# MCU.net
KiCad netlist of a schematic drawn in Altium Designer
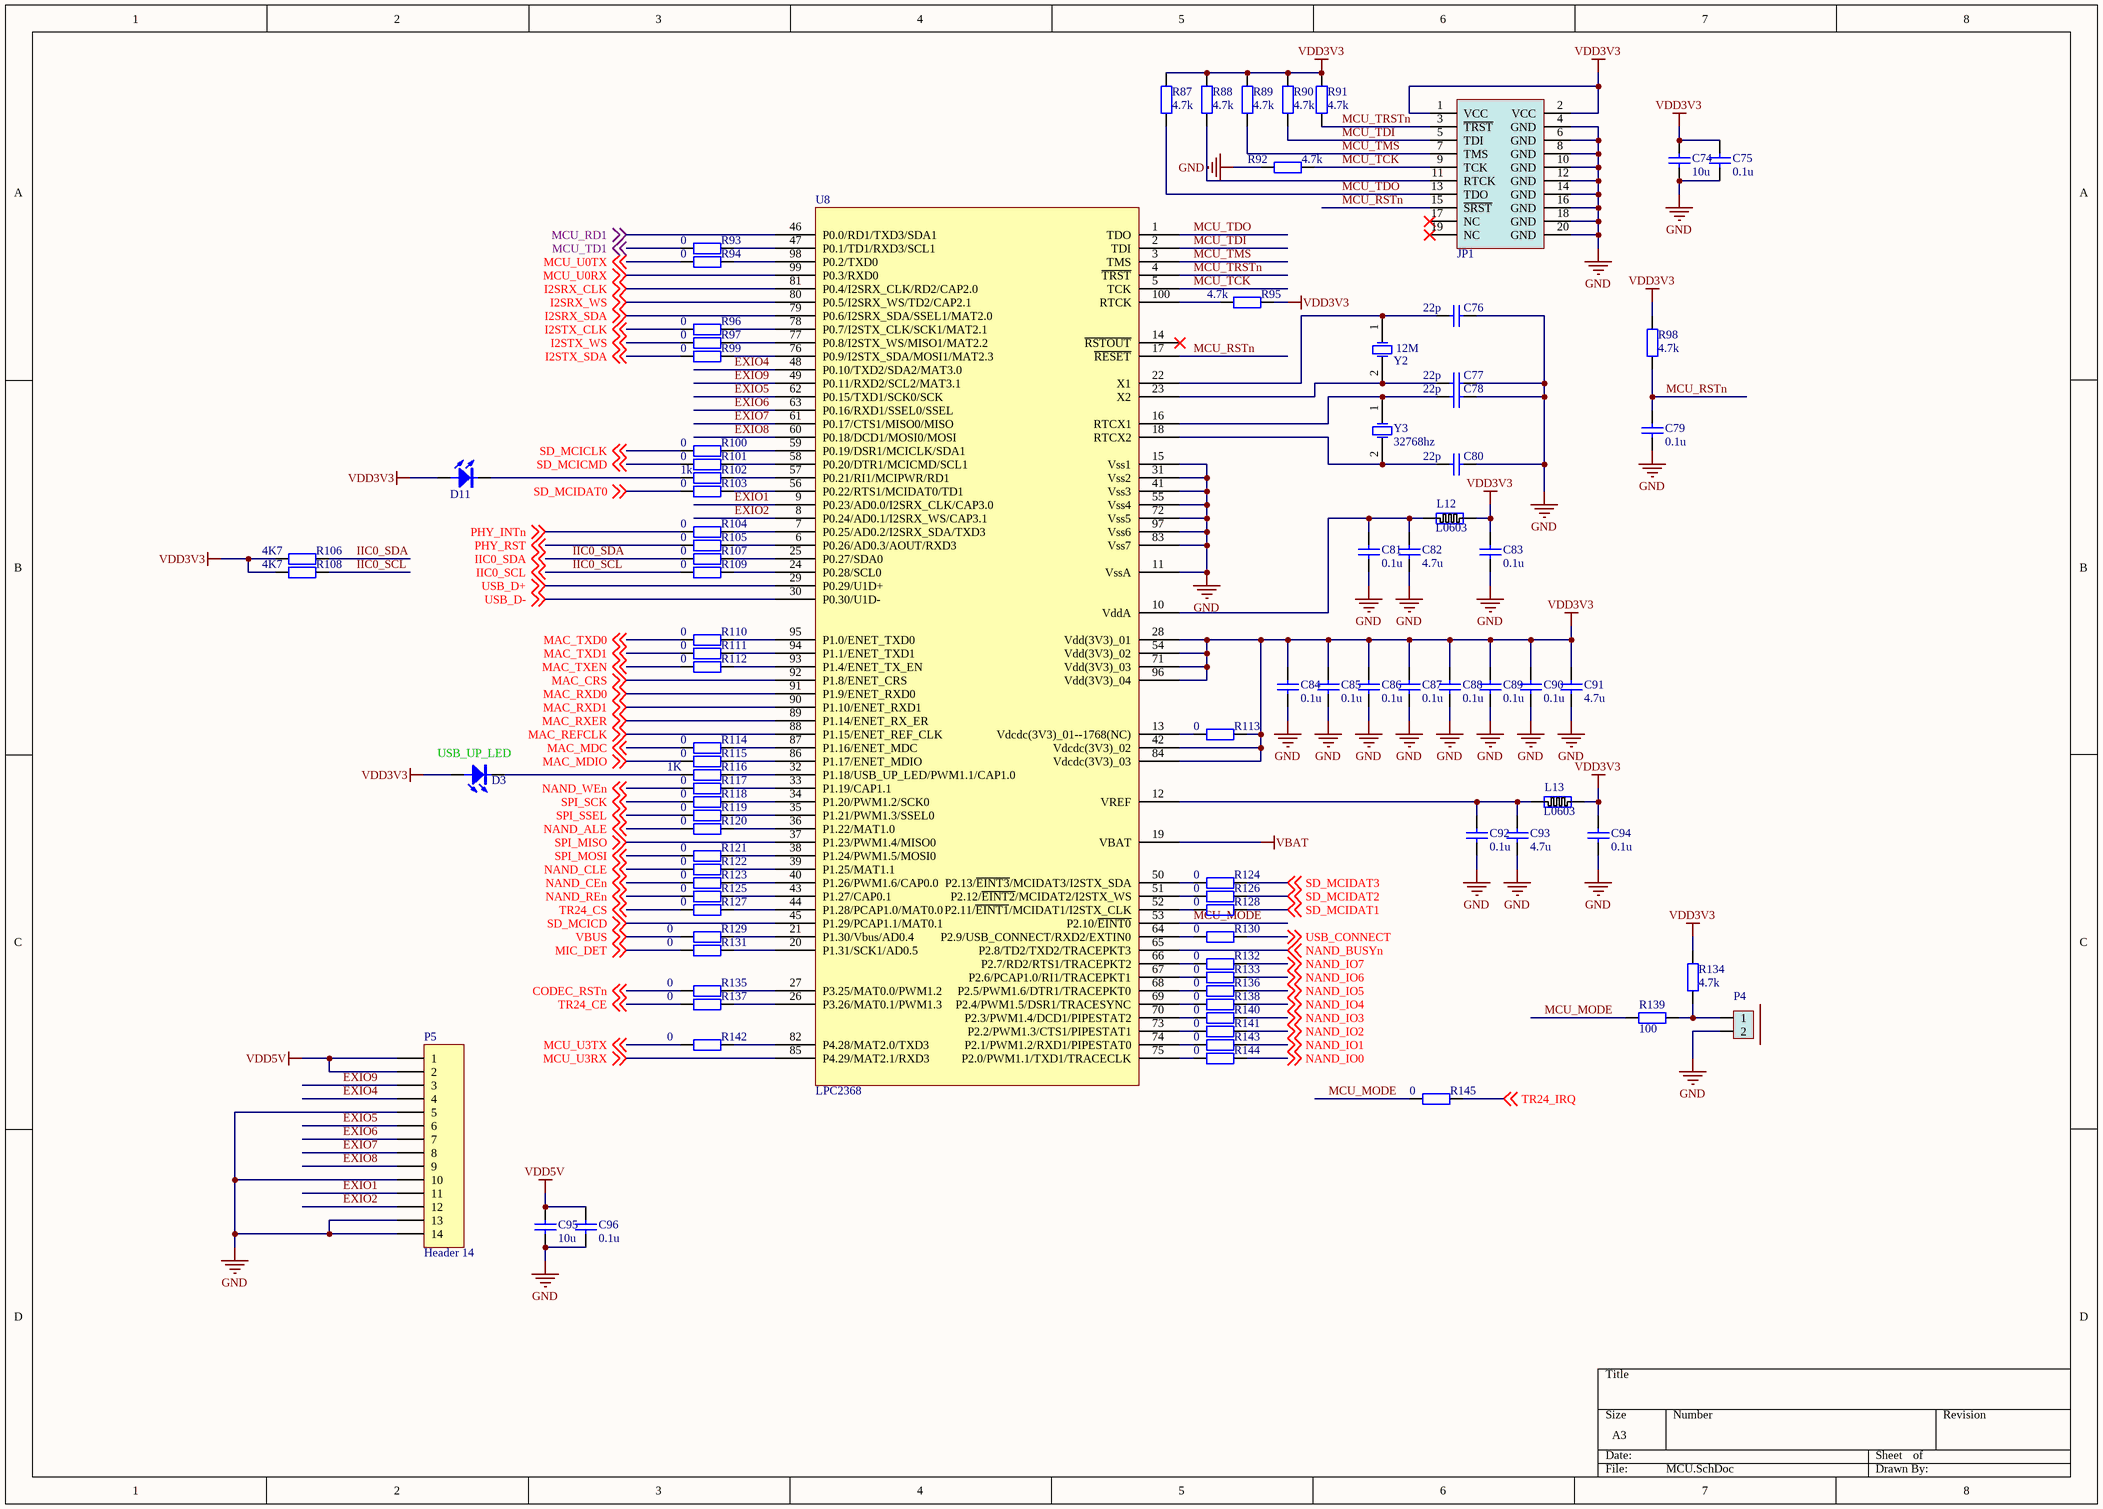
[diagram p0: MCU.SchDoc]

(export (version "E")
  (design (tool "Eeschema 10.0.6"))
  (components
    (comp (ref "C74")
      (value "10u")
      (footprint "C0603")
      (description "0603 Capacitor without Polarity")
      (libsource (lib "lpc2368") (part "CAP0603"))
    )
    (comp (ref "C75")
      (value "0.1u")
      (footprint "C0603")
      (description "0603 Capacitor without Polarity")
      (libsource (lib "lpc2368") (part "CAP0603"))
    )
    (comp (ref "C76")
      (value "22p")
      (footprint "C0603")
      (description "0603 Capacitor without Polarity")
      (libsource (lib "lpc2368") (part "CAP0603"))
    )
    (comp (ref "C77")
      (value "22p")
      (footprint "C0603")
      (description "0603 Capacitor without Polarity")
      (libsource (lib "lpc2368") (part "CAP0603"))
    )
    (comp (ref "C78")
      (value "22p")
      (footprint "C0603")
      (description "0603 Capacitor without Polarity")
      (libsource (lib "lpc2368") (part "CAP0603"))
    )
    (comp (ref "C79")
      (value "0.1u")
      (footprint "C0603")
      (description "0603 Capacitor without Polarity")
      (libsource (lib "lpc2368") (part "CAP0603"))
    )
    (comp (ref "C80")
      (value "22p")
      (footprint "C0603")
      (description "0603 Capacitor without Polarity")
      (libsource (lib "lpc2368") (part "CAP0603"))
    )
    (comp (ref "C81")
      (value "0.1u")
      (footprint "C0603")
      (description "0603 Capacitor without Polarity")
      (libsource (lib "lpc2368") (part "CAP0603"))
    )
    (comp (ref "C82")
      (value "4.7u")
      (footprint "C0603")
      (description "0603 Capacitor without Polarity")
      (libsource (lib "lpc2368") (part "CAP0603"))
    )
    (comp (ref "C83")
      (value "0.1u")
      (footprint "C0603")
      (description "0603 Capacitor without Polarity")
      (libsource (lib "lpc2368") (part "CAP0603"))
    )
    (comp (ref "C84")
      (value "0.1u")
      (footprint "C0603")
      (description "0603 Capacitor without Polarity")
      (libsource (lib "lpc2368") (part "CAP0603"))
    )
    (comp (ref "C85")
      (value "0.1u")
      (footprint "C0603")
      (description "0603 Capacitor without Polarity")
      (libsource (lib "lpc2368") (part "CAP0603"))
    )
    (comp (ref "C86")
      (value "0.1u")
      (footprint "C0603")
      (description "0603 Capacitor without Polarity")
      (libsource (lib "lpc2368") (part "CAP0603"))
    )
    (comp (ref "C87")
      (value "0.1u")
      (footprint "C0603")
      (description "0603 Capacitor without Polarity")
      (libsource (lib "lpc2368") (part "CAP0603"))
    )
    (comp (ref "C88")
      (value "0.1u")
      (footprint "C0603")
      (description "0603 Capacitor without Polarity")
      (libsource (lib "lpc2368") (part "CAP0603"))
    )
    (comp (ref "C89")
      (value "0.1u")
      (footprint "C0603")
      (description "0603 Capacitor without Polarity")
      (libsource (lib "lpc2368") (part "CAP0603"))
    )
    (comp (ref "C90")
      (value "0.1u")
      (footprint "C0603")
      (description "0603 Capacitor without Polarity")
      (libsource (lib "lpc2368") (part "CAP0603"))
    )
    (comp (ref "C91")
      (value "4.7u")
      (footprint "C0603")
      (description "0603 Capacitor without Polarity")
      (libsource (lib "lpc2368") (part "CAP0603"))
    )
    (comp (ref "C92")
      (value "0.1u")
      (footprint "C0603")
      (description "0603 Capacitor without Polarity")
      (libsource (lib "lpc2368") (part "CAP0603"))
    )
    (comp (ref "C93")
      (value "4.7u")
      (footprint "C0603")
      (description "0603 Capacitor without Polarity")
      (libsource (lib "lpc2368") (part "CAP0603"))
    )
    (comp (ref "C94")
      (value "0.1u")
      (footprint "C0603")
      (description "0603 Capacitor without Polarity")
      (libsource (lib "lpc2368") (part "CAP0603"))
    )
    (comp (ref "C95")
      (value "10u")
      (footprint "C0603")
      (description "0603 Capacitor without Polarity")
      (libsource (lib "lpc2368") (part "CAP0603"))
    )
    (comp (ref "C96")
      (value "0.1u")
      (footprint "C0603")
      (description "0603 Capacitor without Polarity")
      (libsource (lib "lpc2368") (part "CAP0603"))
    )
    (comp (ref "D3")
      (value "LED_SMT")
      (footprint "LED0805")
      (description "贴片发光二极管")
      (libsource (lib "lpc2368") (part "LED_SMT"))
    )
    (comp (ref "D11")
      (value "LED_SMT")
      (footprint "LED0805")
      (description "贴片发光二极管")
      (libsource (lib "lpc2368") (part "LED_SMT"))
    )
    (comp (ref "JP1")
      (value "JTAG20")
      (footprint "IDC-20(2.54)IDE")
      (description "JLINK-Interface")
      (libsource (lib "lpc2368") (part "JTAG20"))
    )
    (comp (ref "L12")
      (value "L0603")
      (footprint "L0603")
      (description "0603 Inductor")
      (libsource (lib "lpc2368") (part "L0603"))
    )
    (comp (ref "L13")
      (value "L0603")
      (footprint "L0603")
      (description "0603 Inductor")
      (libsource (lib "lpc2368") (part "L0603"))
    )
    (comp (ref "P4")
      (value "PIN")
      (footprint "SIP2")
      (description "Connectors with two pins")
      (libsource (lib "lpc2368") (part "SIP2"))
    )
    (comp (ref "P5")
      (value "Header 14")
      (footprint "HDR1X14")
      (description "Header, 14-Pin")
      (fields (field (name "PUBLISHER") "Altium Limited"))
      (libsource (lib "Miscellaneous Connectors") (part "Header 14"))
    )
    (comp (ref "R87")
      (value "4.7k")
      (footprint "R0603")
      (description "0603 Resistor")
      (libsource (lib "") (part "RES0603_1"))
    )
    (comp (ref "R88")
      (value "4.7k")
      (footprint "R0603")
      (description "0603 Resistor")
      (libsource (lib "") (part "RES0603_1"))
    )
    (comp (ref "R89")
      (value "4.7k")
      (footprint "R0603")
      (description "0603 Resistor")
      (libsource (lib "") (part "RES0603_1"))
    )
    (comp (ref "R90")
      (value "4.7k")
      (footprint "R0603")
      (description "0603 Resistor")
      (libsource (lib "") (part "RES0603_1"))
    )
    (comp (ref "R91")
      (value "4.7k")
      (footprint "R0603")
      (description "0603 Resistor")
      (libsource (lib "") (part "RES0603_1"))
    )
    (comp (ref "R92")
      (value "4.7k")
      (footprint "R0603")
      (description "0603 Resistor")
      (libsource (lib "") (part "RES0603_2"))
    )
    (comp (ref "R93")
      (value "0")
      (footprint "R0603")
      (description "0603 Resistor")
      (libsource (lib "lpc2368") (part "RES0603"))
    )
    (comp (ref "R94")
      (value "0")
      (footprint "R0603")
      (description "0603 Resistor")
      (libsource (lib "lpc2368") (part "RES0603"))
    )
    (comp (ref "R95")
      (value "4.7k")
      (footprint "R0603")
      (description "0603 Resistor")
      (libsource (lib "lpc2368") (part "RES0603"))
    )
    (comp (ref "R96")
      (value "0")
      (footprint "R0603")
      (description "0603 Resistor")
      (libsource (lib "lpc2368") (part "RES0603"))
    )
    (comp (ref "R97")
      (value "0")
      (footprint "R0603")
      (description "0603 Resistor")
      (libsource (lib "lpc2368") (part "RES0603"))
    )
    (comp (ref "R98")
      (value "4.7k")
      (footprint "R0603")
      (description "0603 Resistor")
      (libsource (lib "") (part "RES0603_1"))
    )
    (comp (ref "R99")
      (value "0")
      (footprint "R0603")
      (description "0603 Resistor")
      (libsource (lib "lpc2368") (part "RES0603"))
    )
    (comp (ref "R100")
      (value "0")
      (footprint "R0603")
      (description "0603 Resistor")
      (libsource (lib "lpc2368") (part "RES0603"))
    )
    (comp (ref "R101")
      (value "0")
      (footprint "R0603")
      (description "0603 Resistor")
      (libsource (lib "lpc2368") (part "RES0603"))
    )
    (comp (ref "R102")
      (value "1k")
      (footprint "R0603")
      (description "0603 Resistor")
      (libsource (lib "lpc2368") (part "RES0603"))
    )
    (comp (ref "R103")
      (value "0")
      (footprint "R0603")
      (description "0603 Resistor")
      (libsource (lib "lpc2368") (part "RES0603"))
    )
    (comp (ref "R104")
      (value "0")
      (footprint "R0603")
      (description "0603 Resistor")
      (libsource (lib "lpc2368") (part "RES0603"))
    )
    (comp (ref "R105")
      (value "0")
      (footprint "R0603")
      (description "0603 Resistor")
      (libsource (lib "lpc2368") (part "RES0603"))
    )
    (comp (ref "R106")
      (value "4K7")
      (footprint "R0603")
      (description "0603 Resistor")
      (libsource (lib "") (part "RES0603_2"))
    )
    (comp (ref "R107")
      (value "0")
      (footprint "R0603")
      (description "0603 Resistor")
      (libsource (lib "lpc2368") (part "RES0603"))
    )
    (comp (ref "R108")
      (value "4K7")
      (footprint "R0603")
      (description "0603 Resistor")
      (libsource (lib "") (part "RES0603_2"))
    )
    (comp (ref "R109")
      (value "0")
      (footprint "R0603")
      (description "0603 Resistor")
      (libsource (lib "lpc2368") (part "RES0603"))
    )
    (comp (ref "R110")
      (value "0")
      (footprint "R0603")
      (description "0603 Resistor")
      (libsource (lib "lpc2368") (part "RES0603"))
    )
    (comp (ref "R111")
      (value "0")
      (footprint "R0603")
      (description "0603 Resistor")
      (libsource (lib "lpc2368") (part "RES0603"))
    )
    (comp (ref "R112")
      (value "0")
      (footprint "R0603")
      (description "0603 Resistor")
      (libsource (lib "lpc2368") (part "RES0603"))
    )
    (comp (ref "R113")
      (value "0")
      (footprint "R0603")
      (description "0603 Resistor")
      (libsource (lib "lpc2368") (part "RES0603"))
    )
    (comp (ref "R114")
      (value "0")
      (footprint "R0603")
      (description "0603 Resistor")
      (libsource (lib "lpc2368") (part "RES0603"))
    )
    (comp (ref "R115")
      (value "0")
      (footprint "R0603")
      (description "0603 Resistor")
      (libsource (lib "lpc2368") (part "RES0603"))
    )
    (comp (ref "R116")
      (value "1K")
      (footprint "R0603")
      (description "0603 Resistor")
      (libsource (lib "lpc2368") (part "RES0603"))
    )
    (comp (ref "R117")
      (value "0")
      (footprint "R0603")
      (description "0603 Resistor")
      (libsource (lib "lpc2368") (part "RES0603"))
    )
    (comp (ref "R118")
      (value "0")
      (footprint "R0603")
      (description "0603 Resistor")
      (libsource (lib "lpc2368") (part "RES0603"))
    )
    (comp (ref "R119")
      (value "0")
      (footprint "R0603")
      (description "0603 Resistor")
      (libsource (lib "lpc2368") (part "RES0603"))
    )
    (comp (ref "R120")
      (value "0")
      (footprint "R0603")
      (description "0603 Resistor")
      (libsource (lib "lpc2368") (part "RES0603"))
    )
    (comp (ref "R121")
      (value "0")
      (footprint "R0603")
      (description "0603 Resistor")
      (libsource (lib "lpc2368") (part "RES0603"))
    )
    (comp (ref "R122")
      (value "0")
      (footprint "R0603")
      (description "0603 Resistor")
      (libsource (lib "lpc2368") (part "RES0603"))
    )
    (comp (ref "R123")
      (value "0")
      (footprint "R0603")
      (description "0603 Resistor")
      (libsource (lib "lpc2368") (part "RES0603"))
    )
    (comp (ref "R124")
      (value "0")
      (footprint "R0603")
      (description "0603 Resistor")
      (libsource (lib "lpc2368") (part "RES0603"))
    )
    (comp (ref "R125")
      (value "0")
      (footprint "R0603")
      (description "0603 Resistor")
      (libsource (lib "lpc2368") (part "RES0603"))
    )
    (comp (ref "R126")
      (value "0")
      (footprint "R0603")
      (description "0603 Resistor")
      (libsource (lib "lpc2368") (part "RES0603"))
    )
    (comp (ref "R127")
      (value "0")
      (footprint "R0603")
      (description "0603 Resistor")
      (libsource (lib "lpc2368") (part "RES0603"))
    )
    (comp (ref "R128")
      (value "0")
      (footprint "R0603")
      (description "0603 Resistor")
      (libsource (lib "lpc2368") (part "RES0603"))
    )
    (comp (ref "R129")
      (value "0")
      (footprint "R0603")
      (description "0603 Resistor")
      (libsource (lib "lpc2368") (part "RES0603"))
    )
    (comp (ref "R130")
      (value "0")
      (footprint "R0603")
      (description "0603 Resistor")
      (libsource (lib "lpc2368") (part "RES0603"))
    )
    (comp (ref "R131")
      (value "0")
      (footprint "R0603")
      (description "0603 Resistor")
      (libsource (lib "lpc2368") (part "RES0603"))
    )
    (comp (ref "R132")
      (value "0")
      (footprint "R0603")
      (description "0603 Resistor")
      (libsource (lib "lpc2368") (part "RES0603"))
    )
    (comp (ref "R133")
      (value "0")
      (footprint "R0603")
      (description "0603 Resistor")
      (libsource (lib "lpc2368") (part "RES0603"))
    )
    (comp (ref "R134")
      (value "4.7k")
      (footprint "R0603")
      (description "0603 Resistor")
      (libsource (lib "") (part "RES0603_1"))
    )
    (comp (ref "R135")
      (value "0")
      (footprint "R0603")
      (description "0603 Resistor")
      (libsource (lib "lpc2368") (part "RES0603"))
    )
    (comp (ref "R136")
      (value "0")
      (footprint "R0603")
      (description "0603 Resistor")
      (libsource (lib "lpc2368") (part "RES0603"))
    )
    (comp (ref "R137")
      (value "0")
      (footprint "R0603")
      (description "0603 Resistor")
      (libsource (lib "lpc2368") (part "RES0603"))
    )
    (comp (ref "R138")
      (value "0")
      (footprint "R0603")
      (description "0603 Resistor")
      (libsource (lib "lpc2368") (part "RES0603"))
    )
    (comp (ref "R139")
      (value "100")
      (footprint "R0603")
      (description "0603 Resistor")
      (libsource (lib "") (part "RES0603_2"))
    )
    (comp (ref "R140")
      (value "0")
      (footprint "R0603")
      (description "0603 Resistor")
      (libsource (lib "lpc2368") (part "RES0603"))
    )
    (comp (ref "R141")
      (value "0")
      (footprint "R0603")
      (description "0603 Resistor")
      (libsource (lib "lpc2368") (part "RES0603"))
    )
    (comp (ref "R142")
      (value "0")
      (footprint "R0603")
      (description "0603 Resistor")
      (libsource (lib "lpc2368") (part "RES0603"))
    )
    (comp (ref "R143")
      (value "0")
      (footprint "R0603")
      (description "0603 Resistor")
      (libsource (lib "lpc2368") (part "RES0603"))
    )
    (comp (ref "R144")
      (value "0")
      (footprint "R0603")
      (description "0603 Resistor")
      (libsource (lib "lpc2368") (part "RES0603"))
    )
    (comp (ref "R145")
      (value "0")
      (footprint "R0603")
      (description "0603 Resistor")
      (libsource (lib "lpc2368") (part "RES0603"))
    )
    (comp (ref "U8")
      (value "LPC2368")
      (footprint "QFP100-I20-605605")
      (libsource (lib "lpc2368") (part "LPC2368"))
    )
    (comp (ref "Y2")
      (value "12M")
      (footprint "XTAL-SMD-LP")
      (description "2Pin晶振")
      (libsource (lib "lpc2368") (part "XTAL"))
    )
    (comp (ref "Y3")
      (value "32768hz")
      (footprint "XTAL32768")
      (description "2Pin晶振")
      (libsource (lib "lpc2368") (part "XTAL32768"))
    )
  )
  (nets
    (net (code "1") (name "/EXIO1") (class "Default")
      (node (ref "P5") (pin "11") (pinfunction "11_11") (pintype "passive"))
      (node (ref "U8") (pin "9") (pinfunction "P0.23/AD0.0/I2SRX_CLK/CAP3.0_9") (pintype "passive"))
    )
    (net (code "2") (name "/EXIO2") (class "Default")
      (node (ref "P5") (pin "12") (pinfunction "12_12") (pintype "passive"))
      (node (ref "U8") (pin "8") (pinfunction "P0.24/AD0.1/I2SRX_WS/CAP3.1_8") (pintype "passive"))
    )
    (net (code "3") (name "/EXIO4") (class "Default")
      (node (ref "P5") (pin "4") (pinfunction "4_4") (pintype "passive"))
      (node (ref "U8") (pin "48") (pinfunction "P0.10/TXD2/SDA2/MAT3.0_48") (pintype "passive"))
    )
    (net (code "4") (name "/EXIO5") (class "Default")
      (node (ref "P5") (pin "6") (pinfunction "6_6") (pintype "passive"))
      (node (ref "U8") (pin "62") (pinfunction "P0.15/TXD1/SCK0/SCK_62") (pintype "passive"))
    )
    (net (code "5") (name "/EXIO6") (class "Default")
      (node (ref "P5") (pin "7") (pinfunction "7_7") (pintype "passive"))
      (node (ref "U8") (pin "63") (pinfunction "P0.16/RXD1/SSEL0/SSEL_63") (pintype "passive"))
    )
    (net (code "6") (name "/EXIO7") (class "Default")
      (node (ref "P5") (pin "8") (pinfunction "8_8") (pintype "passive"))
      (node (ref "U8") (pin "61") (pinfunction "P0.17/CTS1/MISO0/MISO_61") (pintype "passive"))
    )
    (net (code "7") (name "/EXIO8") (class "Default")
      (node (ref "P5") (pin "9") (pinfunction "9_9") (pintype "passive"))
      (node (ref "U8") (pin "60") (pinfunction "P0.18/DCD1/MOSI0/MOSI_60") (pintype "passive"))
    )
    (net (code "8") (name "/EXIO9") (class "Default")
      (node (ref "P5") (pin "3") (pinfunction "3_3") (pintype "passive"))
      (node (ref "U8") (pin "49") (pinfunction "P0.11/RXD2/SCL2/MAT3.1_49") (pintype "passive"))
    )
    (net (code "9") (name "/MCU_MODE") (class "Default")
      (node (ref "R139") (pin "2") (pinfunction "2_2") (pintype "passive"))
      (node (ref "R145") (pin "1") (pinfunction "1_1") (pintype "passive"))
      (node (ref "U8") (pin "53") (pinfunction "P2.10/~{EINT0}_53") (pintype "passive"))
    )
    (net (code "10") (name "/MCU_RSTn") (class "Default")
      (node (ref "C79") (pin "2") (pinfunction "2_2") (pintype "passive"))
      (node (ref "JP1") (pin "15") (pinfunction "~{SRST}_15") (pintype "passive"))
      (node (ref "R98") (pin "1") (pinfunction "1_1") (pintype "passive"))
      (node (ref "U8") (pin "17") (pinfunction "~{RESET}_17") (pintype "passive"))
    )
    (net (code "11") (name "/MCU_TCK") (class "Default")
      (node (ref "JP1") (pin "9") (pinfunction "TCK_9") (pintype "passive"))
      (node (ref "R92") (pin "1") (pinfunction "1_1") (pintype "passive"))
      (node (ref "U8") (pin "5") (pinfunction "TCK_5") (pintype "passive"))
    )
    (net (code "12") (name "/MCU_TDI") (class "Default")
      (node (ref "JP1") (pin "5") (pinfunction "TDI_5") (pintype "passive"))
      (node (ref "R90") (pin "1") (pinfunction "1_1") (pintype "passive"))
      (node (ref "U8") (pin "2") (pinfunction "TDI_2") (pintype "passive"))
    )
    (net (code "13") (name "/MCU_TDO") (class "Default")
      (node (ref "JP1") (pin "13") (pinfunction "TDO_13") (pintype "passive"))
      (node (ref "R87") (pin "1") (pinfunction "1_1") (pintype "passive"))
      (node (ref "U8") (pin "1") (pinfunction "TDO_1") (pintype "passive"))
    )
    (net (code "14") (name "/MCU_TMS") (class "Default")
      (node (ref "JP1") (pin "7") (pinfunction "TMS_7") (pintype "passive"))
      (node (ref "R89") (pin "1") (pinfunction "1_1") (pintype "passive"))
      (node (ref "U8") (pin "3") (pinfunction "TMS_3") (pintype "passive"))
    )
    (net (code "15") (name "/MCU_TRSTn") (class "Default")
      (node (ref "JP1") (pin "3") (pinfunction "~{TRST}_3") (pintype "passive"))
      (node (ref "R91") (pin "1") (pinfunction "1_1") (pintype "passive"))
      (node (ref "U8") (pin "4") (pinfunction "~{TRST}_4") (pintype "passive"))
    )
    (net (code "16") (name "CODEC_RSTn") (class "Default")
      (node (ref "R135") (pin "1") (pinfunction "1_1") (pintype "passive"))
    )
    (net (code "17") (name "GND") (class "Default")
      (node (ref "C74") (pin "1") (pinfunction "1_1") (pintype "passive"))
      (node (ref "C75") (pin "1") (pinfunction "1_1") (pintype "passive"))
      (node (ref "C76") (pin "1") (pinfunction "1_1") (pintype "passive"))
      (node (ref "C77") (pin "1") (pinfunction "1_1") (pintype "passive"))
      (node (ref "C78") (pin "1") (pinfunction "1_1") (pintype "passive"))
      (node (ref "C79") (pin "1") (pinfunction "1_1") (pintype "passive"))
      (node (ref "C80") (pin "1") (pinfunction "1_1") (pintype "passive"))
      (node (ref "C81") (pin "1") (pinfunction "1_1") (pintype "passive"))
      (node (ref "C82") (pin "1") (pinfunction "1_1") (pintype "passive"))
      (node (ref "C83") (pin "1") (pinfunction "1_1") (pintype "passive"))
      (node (ref "C84") (pin "1") (pinfunction "1_1") (pintype "passive"))
      (node (ref "C85") (pin "1") (pinfunction "1_1") (pintype "passive"))
      (node (ref "C86") (pin "1") (pinfunction "1_1") (pintype "passive"))
      (node (ref "C87") (pin "1") (pinfunction "1_1") (pintype "passive"))
      (node (ref "C88") (pin "1") (pinfunction "1_1") (pintype "passive"))
      (node (ref "C89") (pin "1") (pinfunction "1_1") (pintype "passive"))
      (node (ref "C90") (pin "1") (pinfunction "1_1") (pintype "passive"))
      (node (ref "C91") (pin "1") (pinfunction "1_1") (pintype "passive"))
      (node (ref "C92") (pin "1") (pinfunction "1_1") (pintype "passive"))
      (node (ref "C93") (pin "1") (pinfunction "1_1") (pintype "passive"))
      (node (ref "C94") (pin "1") (pinfunction "1_1") (pintype "passive"))
      (node (ref "C95") (pin "1") (pinfunction "1_1") (pintype "passive"))
      (node (ref "C96") (pin "1") (pinfunction "1_1") (pintype "passive"))
      (node (ref "JP1") (pin "10") (pinfunction "GND_10") (pintype "passive"))
      (node (ref "JP1") (pin "12") (pinfunction "GND_12") (pintype "passive"))
      (node (ref "JP1") (pin "14") (pinfunction "GND_14") (pintype "passive"))
      (node (ref "JP1") (pin "16") (pinfunction "GND_16") (pintype "passive"))
      (node (ref "JP1") (pin "18") (pinfunction "GND_18") (pintype "passive"))
      (node (ref "JP1") (pin "20") (pinfunction "GND_20") (pintype "passive"))
      (node (ref "JP1") (pin "4") (pinfunction "GND_4") (pintype "passive"))
      (node (ref "JP1") (pin "6") (pinfunction "GND_6") (pintype "passive"))
      (node (ref "JP1") (pin "8") (pinfunction "GND_8") (pintype "passive"))
      (node (ref "P4") (pin "2") (pinfunction "2_2") (pintype "passive"))
      (node (ref "P5") (pin "10") (pinfunction "10_10") (pintype "passive"))
      (node (ref "P5") (pin "13") (pinfunction "13_13") (pintype "passive"))
      (node (ref "P5") (pin "14") (pinfunction "14_14") (pintype "passive"))
      (node (ref "P5") (pin "5") (pinfunction "5_5") (pintype "passive"))
      (node (ref "R92") (pin "2") (pinfunction "2_2") (pintype "passive"))
      (node (ref "U8") (pin "11") (pinfunction "VssA_11") (pintype "passive"))
      (node (ref "U8") (pin "15") (pinfunction "Vss1_15") (pintype "passive"))
      (node (ref "U8") (pin "31") (pinfunction "Vss2_31") (pintype "passive"))
      (node (ref "U8") (pin "41") (pinfunction "Vss3_41") (pintype "passive"))
      (node (ref "U8") (pin "55") (pinfunction "Vss4_55") (pintype "passive"))
      (node (ref "U8") (pin "72") (pinfunction "Vss5_72") (pintype "passive"))
      (node (ref "U8") (pin "83") (pinfunction "Vss7_83") (pintype "passive"))
      (node (ref "U8") (pin "97") (pinfunction "Vss6_97") (pintype "passive"))
    )
    (net (code "18") (name "I2SRX_CLK") (class "Default")
      (node (ref "U8") (pin "81") (pinfunction "P0.4/I2SRX_CLK/RD2/CAP2.0_81") (pintype "passive"))
    )
    (net (code "19") (name "I2SRX_SDA") (class "Default")
      (node (ref "U8") (pin "79") (pinfunction "P0.6/I2SRX_SDA/SSEL1/MAT2.0_79") (pintype "passive"))
    )
    (net (code "20") (name "I2SRX_WS") (class "Default")
      (node (ref "U8") (pin "80") (pinfunction "P0.5/I2SRX_WS/TD2/CAP2.1_80") (pintype "passive"))
    )
    (net (code "21") (name "I2STX_CLK") (class "Default")
      (node (ref "R96") (pin "1") (pinfunction "1_1") (pintype "passive"))
    )
    (net (code "22") (name "I2STX_SDA") (class "Default")
      (node (ref "R99") (pin "1") (pinfunction "1_1") (pintype "passive"))
    )
    (net (code "23") (name "I2STX_WS") (class "Default")
      (node (ref "R97") (pin "1") (pinfunction "1_1") (pintype "passive"))
    )
    (net (code "24") (name "IIC0_SCL") (class "Default")
      (node (ref "R108") (pin "1") (pinfunction "1_1") (pintype "passive"))
      (node (ref "R109") (pin "1") (pinfunction "1_1") (pintype "passive"))
    )
    (net (code "25") (name "IIC0_SDA") (class "Default")
      (node (ref "R106") (pin "1") (pinfunction "1_1") (pintype "passive"))
      (node (ref "R107") (pin "1") (pinfunction "1_1") (pintype "passive"))
    )
    (net (code "26") (name "MAC_CRS") (class "Default")
      (node (ref "U8") (pin "92") (pinfunction "P1.8/ENET_CRS_92") (pintype "passive"))
    )
    (net (code "27") (name "MAC_MDC") (class "Default")
      (node (ref "R114") (pin "1") (pinfunction "1_1") (pintype "passive"))
    )
    (net (code "28") (name "MAC_MDIO") (class "Default")
      (node (ref "R115") (pin "1") (pinfunction "1_1") (pintype "passive"))
    )
    (net (code "29") (name "MAC_REFCLK") (class "Default")
      (node (ref "U8") (pin "88") (pinfunction "P1.15/ENET_REF_CLK_88") (pintype "passive"))
    )
    (net (code "30") (name "MAC_RXD0") (class "Default")
      (node (ref "U8") (pin "91") (pinfunction "P1.9/ENET_RXD0_91") (pintype "passive"))
    )
    (net (code "31") (name "MAC_RXD1") (class "Default")
      (node (ref "U8") (pin "90") (pinfunction "P1.10/ENET_RXD1_90") (pintype "passive"))
    )
    (net (code "32") (name "MAC_RXER") (class "Default")
      (node (ref "U8") (pin "89") (pinfunction "P1.14/ENET_RX_ER_89") (pintype "passive"))
    )
    (net (code "33") (name "MAC_TXD0") (class "Default")
      (node (ref "R110") (pin "1") (pinfunction "1_1") (pintype "passive"))
    )
    (net (code "34") (name "MAC_TXD1") (class "Default")
      (node (ref "R111") (pin "1") (pinfunction "1_1") (pintype "passive"))
    )
    (net (code "35") (name "MAC_TXEN") (class "Default")
      (node (ref "R112") (pin "1") (pinfunction "1_1") (pintype "passive"))
    )
    (net (code "36") (name "MCU_RD1") (class "Default")
      (node (ref "U8") (pin "46") (pinfunction "P0.0/RD1/TXD3/SDA1_46") (pintype "passive"))
    )
    (net (code "37") (name "MCU_TD1") (class "Default")
      (node (ref "R93") (pin "1") (pinfunction "1_1") (pintype "passive"))
    )
    (net (code "38") (name "MCU_U0RX") (class "Default")
      (node (ref "U8") (pin "99") (pinfunction "P0.3/RXD0_99") (pintype "passive"))
    )
    (net (code "39") (name "MCU_U0TX") (class "Default")
      (node (ref "R94") (pin "1") (pinfunction "1_1") (pintype "passive"))
    )
    (net (code "40") (name "MCU_U3RX") (class "Default")
      (node (ref "U8") (pin "85") (pinfunction "P4.29/MAT2.1/RXD3_85") (pintype "passive"))
    )
    (net (code "41") (name "MCU_U3TX") (class "Default")
      (node (ref "R142") (pin "1") (pinfunction "1_1") (pintype "passive"))
    )
    (net (code "42") (name "MIC_DET") (class "Default")
      (node (ref "R131") (pin "1") (pinfunction "1_1") (pintype "passive"))
    )
    (net (code "43") (name "NAND_ALE") (class "Default")
      (node (ref "R120") (pin "1") (pinfunction "1_1") (pintype "passive"))
    )
    (net (code "44") (name "NAND_BUSYn") (class "Default")
      (node (ref "U8") (pin "65") (pinfunction "P2.8/TD2/TXD2/TRACEPKT3_65") (pintype "passive"))
    )
    (net (code "45") (name "NAND_CEn") (class "Default")
      (node (ref "R123") (pin "1") (pinfunction "1_1") (pintype "passive"))
    )
    (net (code "46") (name "NAND_CLE") (class "Default")
      (node (ref "R122") (pin "1") (pinfunction "1_1") (pintype "passive"))
    )
    (net (code "47") (name "NAND_IO0") (class "Default")
      (node (ref "R144") (pin "2") (pinfunction "2_2") (pintype "passive"))
    )
    (net (code "48") (name "NAND_IO1") (class "Default")
      (node (ref "R143") (pin "2") (pinfunction "2_2") (pintype "passive"))
    )
    (net (code "49") (name "NAND_IO2") (class "Default")
      (node (ref "R141") (pin "2") (pinfunction "2_2") (pintype "passive"))
    )
    (net (code "50") (name "NAND_IO3") (class "Default")
      (node (ref "R140") (pin "2") (pinfunction "2_2") (pintype "passive"))
    )
    (net (code "51") (name "NAND_IO4") (class "Default")
      (node (ref "R138") (pin "2") (pinfunction "2_2") (pintype "passive"))
    )
    (net (code "52") (name "NAND_IO5") (class "Default")
      (node (ref "R136") (pin "2") (pinfunction "2_2") (pintype "passive"))
    )
    (net (code "53") (name "NAND_IO6") (class "Default")
      (node (ref "R133") (pin "2") (pinfunction "2_2") (pintype "passive"))
    )
    (net (code "54") (name "NAND_IO7") (class "Default")
      (node (ref "R132") (pin "2") (pinfunction "2_2") (pintype "passive"))
    )
    (net (code "55") (name "NAND_REn") (class "Default")
      (node (ref "R125") (pin "1") (pinfunction "1_1") (pintype "passive"))
    )
    (net (code "56") (name "NAND_WEn") (class "Default")
      (node (ref "R117") (pin "1") (pinfunction "1_1") (pintype "passive"))
    )
    (net (code "57") (name "Net-(D3-PadK)") (class "Default")
      (node (ref "D3") (pin "K") (pinfunction "K_K") (pintype "passive"))
      (node (ref "R116") (pin "1") (pinfunction "1_1") (pintype "passive"))
    )
    (net (code "58") (name "Net-(D11-PadK)") (class "Default")
      (node (ref "D11") (pin "K") (pinfunction "K_K") (pintype "passive"))
      (node (ref "R102") (pin "1") (pinfunction "1_1") (pintype "passive"))
    )
    (net (code "59") (name "Net-(JP1-RTCK)") (class "Default")
      (node (ref "JP1") (pin "11") (pinfunction "RTCK_11") (pintype "passive"))
      (node (ref "R88") (pin "1") (pinfunction "1_1") (pintype "passive"))
    )
    (net (code "60") (name "Net-(P4-Pad1)") (class "Default")
      (node (ref "P4") (pin "1") (pinfunction "1_1") (pintype "passive"))
      (node (ref "R134") (pin "1") (pinfunction "1_1") (pintype "passive"))
      (node (ref "R139") (pin "1") (pinfunction "1_1") (pintype "passive"))
    )
    (net (code "61") (name "Net-(U8-P0.1{slash}TD1{slash}RXD3{slash}SCL1)") (class "Default")
      (node (ref "R93") (pin "2") (pinfunction "2_2") (pintype "passive"))
      (node (ref "U8") (pin "47") (pinfunction "P0.1/TD1/RXD3/SCL1_47") (pintype "passive"))
    )
    (net (code "62") (name "Net-(U8-P0.2{slash}TXD0)") (class "Default")
      (node (ref "R94") (pin "2") (pinfunction "2_2") (pintype "passive"))
      (node (ref "U8") (pin "98") (pinfunction "P0.2/TXD0_98") (pintype "passive"))
    )
    (net (code "63") (name "Net-(U8-P0.7{slash}I2STX_CLK{slash}SCK1{slash}MAT2.1)") (class "Default")
      (node (ref "R96") (pin "2") (pinfunction "2_2") (pintype "passive"))
      (node (ref "U8") (pin "78") (pinfunction "P0.7/I2STX_CLK/SCK1/MAT2.1_78") (pintype "passive"))
    )
    (net (code "64") (name "Net-(U8-P0.8{slash}I2STX_WS{slash}MISO1{slash}MAT2.2)") (class "Default")
      (node (ref "R97") (pin "2") (pinfunction "2_2") (pintype "passive"))
      (node (ref "U8") (pin "77") (pinfunction "P0.8/I2STX_WS/MISO1/MAT2.2_77") (pintype "passive"))
    )
    (net (code "65") (name "Net-(U8-P0.9{slash}I2STX_SDA{slash}MOSI1{slash}MAT2.3)") (class "Default")
      (node (ref "R99") (pin "2") (pinfunction "2_2") (pintype "passive"))
      (node (ref "U8") (pin "76") (pinfunction "P0.9/I2STX_SDA/MOSI1/MAT2.3_76") (pintype "passive"))
    )
    (net (code "66") (name "Net-(U8-P0.19{slash}DSR1{slash}MCICLK{slash}SDA1)") (class "Default")
      (node (ref "R100") (pin "2") (pinfunction "2_2") (pintype "passive"))
      (node (ref "U8") (pin "59") (pinfunction "P0.19/DSR1/MCICLK/SDA1_59") (pintype "passive"))
    )
    (net (code "67") (name "Net-(U8-P0.20{slash}DTR1{slash}MCICMD{slash}SCL1)") (class "Default")
      (node (ref "R101") (pin "2") (pinfunction "2_2") (pintype "passive"))
      (node (ref "U8") (pin "58") (pinfunction "P0.20/DTR1/MCICMD/SCL1_58") (pintype "passive"))
    )
    (net (code "68") (name "Net-(U8-P0.21{slash}RI1{slash}MCIPWR{slash}RD1)") (class "Default")
      (node (ref "R102") (pin "2") (pinfunction "2_2") (pintype "passive"))
      (node (ref "U8") (pin "57") (pinfunction "P0.21/RI1/MCIPWR/RD1_57") (pintype "passive"))
    )
    (net (code "69") (name "Net-(U8-P0.22{slash}RTS1{slash}MCIDAT0{slash}TD1)") (class "Default")
      (node (ref "R103") (pin "2") (pinfunction "2_2") (pintype "passive"))
      (node (ref "U8") (pin "56") (pinfunction "P0.22/RTS1/MCIDAT0/TD1_56") (pintype "passive"))
    )
    (net (code "70") (name "Net-(U8-P0.25{slash}AD0.2{slash}I2SRX_SDA{slash}TXD3)") (class "Default")
      (node (ref "R104") (pin "2") (pinfunction "2_2") (pintype "passive"))
      (node (ref "U8") (pin "7") (pinfunction "P0.25/AD0.2/I2SRX_SDA/TXD3_7") (pintype "passive"))
    )
    (net (code "71") (name "Net-(U8-P0.26{slash}AD0.3{slash}AOUT{slash}RXD3)") (class "Default")
      (node (ref "R105") (pin "2") (pinfunction "2_2") (pintype "passive"))
      (node (ref "U8") (pin "6") (pinfunction "P0.26/AD0.3/AOUT/RXD3_6") (pintype "passive"))
    )
    (net (code "72") (name "Net-(U8-P0.27{slash}SDA0)") (class "Default")
      (node (ref "R107") (pin "2") (pinfunction "2_2") (pintype "passive"))
      (node (ref "U8") (pin "25") (pinfunction "P0.27/SDA0_25") (pintype "passive"))
    )
    (net (code "73") (name "Net-(U8-P0.28{slash}SCL0)") (class "Default")
      (node (ref "R109") (pin "2") (pinfunction "2_2") (pintype "passive"))
      (node (ref "U8") (pin "24") (pinfunction "P0.28/SCL0_24") (pintype "passive"))
    )
    (net (code "74") (name "Net-(U8-P1.0{slash}ENET_TXD0)") (class "Default")
      (node (ref "R110") (pin "2") (pinfunction "2_2") (pintype "passive"))
      (node (ref "U8") (pin "95") (pinfunction "P1.0/ENET_TXD0_95") (pintype "passive"))
    )
    (net (code "75") (name "Net-(U8-P1.1{slash}ENET_TXD1)") (class "Default")
      (node (ref "R111") (pin "2") (pinfunction "2_2") (pintype "passive"))
      (node (ref "U8") (pin "94") (pinfunction "P1.1/ENET_TXD1_94") (pintype "passive"))
    )
    (net (code "76") (name "Net-(U8-P1.4{slash}ENET_TX_EN)") (class "Default")
      (node (ref "R112") (pin "2") (pinfunction "2_2") (pintype "passive"))
      (node (ref "U8") (pin "93") (pinfunction "P1.4/ENET_TX_EN_93") (pintype "passive"))
    )
    (net (code "77") (name "Net-(U8-P1.16{slash}ENET_MDC)") (class "Default")
      (node (ref "R114") (pin "2") (pinfunction "2_2") (pintype "passive"))
      (node (ref "U8") (pin "87") (pinfunction "P1.16/ENET_MDC_87") (pintype "passive"))
    )
    (net (code "78") (name "Net-(U8-P1.17{slash}ENET_MDIO)") (class "Default")
      (node (ref "R115") (pin "2") (pinfunction "2_2") (pintype "passive"))
      (node (ref "U8") (pin "86") (pinfunction "P1.17/ENET_MDIO_86") (pintype "passive"))
    )
    (net (code "79") (name "Net-(U8-P1.18{slash}USB_UP_LED{slash}PWM1.1{slash}CAP1.0)") (class "Default")
      (node (ref "R116") (pin "2") (pinfunction "2_2") (pintype "passive"))
      (node (ref "U8") (pin "32") (pinfunction "P1.18/USB_UP_LED/PWM1.1/CAP1.0_32") (pintype "passive"))
    )
    (net (code "80") (name "Net-(U8-P1.19{slash}CAP1.1)") (class "Default")
      (node (ref "R117") (pin "2") (pinfunction "2_2") (pintype "passive"))
      (node (ref "U8") (pin "33") (pinfunction "P1.19/CAP1.1_33") (pintype "passive"))
    )
    (net (code "81") (name "Net-(U8-P1.20{slash}PWM1.2{slash}SCK0)") (class "Default")
      (node (ref "R118") (pin "2") (pinfunction "2_2") (pintype "passive"))
      (node (ref "U8") (pin "34") (pinfunction "P1.20/PWM1.2/SCK0_34") (pintype "passive"))
    )
    (net (code "82") (name "Net-(U8-P1.21{slash}PWM1.3{slash}SSEL0)") (class "Default")
      (node (ref "R119") (pin "2") (pinfunction "2_2") (pintype "passive"))
      (node (ref "U8") (pin "35") (pinfunction "P1.21/PWM1.3/SSEL0_35") (pintype "passive"))
    )
    (net (code "83") (name "Net-(U8-P1.22{slash}MAT1.0)") (class "Default")
      (node (ref "R120") (pin "2") (pinfunction "2_2") (pintype "passive"))
      (node (ref "U8") (pin "36") (pinfunction "P1.22/MAT1.0_36") (pintype "passive"))
    )
    (net (code "84") (name "Net-(U8-P1.24{slash}PWM1.5{slash}MOSI0)") (class "Default")
      (node (ref "R121") (pin "2") (pinfunction "2_2") (pintype "passive"))
      (node (ref "U8") (pin "38") (pinfunction "P1.24/PWM1.5/MOSI0_38") (pintype "passive"))
    )
    (net (code "85") (name "Net-(U8-P1.25{slash}MAT1.1)") (class "Default")
      (node (ref "R122") (pin "2") (pinfunction "2_2") (pintype "passive"))
      (node (ref "U8") (pin "39") (pinfunction "P1.25/MAT1.1_39") (pintype "passive"))
    )
    (net (code "86") (name "Net-(U8-P1.26{slash}PWM1.6{slash}CAP0.0)") (class "Default")
      (node (ref "R123") (pin "2") (pinfunction "2_2") (pintype "passive"))
      (node (ref "U8") (pin "40") (pinfunction "P1.26/PWM1.6/CAP0.0_40") (pintype "passive"))
    )
    (net (code "87") (name "Net-(U8-P1.27{slash}CAP0.1)") (class "Default")
      (node (ref "R125") (pin "2") (pinfunction "2_2") (pintype "passive"))
      (node (ref "U8") (pin "43") (pinfunction "P1.27/CAP0.1_43") (pintype "passive"))
    )
    (net (code "88") (name "Net-(U8-P1.28{slash}PCAP1.0{slash}MAT0.0)") (class "Default")
      (node (ref "R127") (pin "2") (pinfunction "2_2") (pintype "passive"))
      (node (ref "U8") (pin "44") (pinfunction "P1.28/PCAP1.0/MAT0.0_44") (pintype "passive"))
    )
    (net (code "89") (name "Net-(U8-P1.30{slash}Vbus{slash}AD0.4)") (class "Default")
      (node (ref "R129") (pin "2") (pinfunction "2_2") (pintype "passive"))
      (node (ref "U8") (pin "21") (pinfunction "P1.30/Vbus/AD0.4_21") (pintype "passive"))
    )
    (net (code "90") (name "Net-(U8-P1.31{slash}SCK1{slash}AD0.5)") (class "Default")
      (node (ref "R131") (pin "2") (pinfunction "2_2") (pintype "passive"))
      (node (ref "U8") (pin "20") (pinfunction "P1.31/SCK1/AD0.5_20") (pintype "passive"))
    )
    (net (code "91") (name "Net-(U8-P2.0{slash}PWM1.1{slash}TXD1{slash}TRACECLK)") (class "Default")
      (node (ref "R144") (pin "1") (pinfunction "1_1") (pintype "passive"))
      (node (ref "U8") (pin "75") (pinfunction "P2.0/PWM1.1/TXD1/TRACECLK_75") (pintype "passive"))
    )
    (net (code "92") (name "Net-(U8-P2.1{slash}PWM1.2{slash}RXD1{slash}PIPESTAT0)") (class "Default")
      (node (ref "R143") (pin "1") (pinfunction "1_1") (pintype "passive"))
      (node (ref "U8") (pin "74") (pinfunction "P2.1/PWM1.2/RXD1/PIPESTAT0_74") (pintype "passive"))
    )
    (net (code "93") (name "Net-(U8-P2.2{slash}PWM1.3{slash}CTS1{slash}PIPESTAT1)") (class "Default")
      (node (ref "R141") (pin "1") (pinfunction "1_1") (pintype "passive"))
      (node (ref "U8") (pin "73") (pinfunction "P2.2/PWM1.3/CTS1/PIPESTAT1_73") (pintype "passive"))
    )
    (net (code "94") (name "Net-(U8-P2.3{slash}PWM1.4{slash}DCD1{slash}PIPESTAT2)") (class "Default")
      (node (ref "R140") (pin "1") (pinfunction "1_1") (pintype "passive"))
      (node (ref "U8") (pin "70") (pinfunction "P2.3/PWM1.4/DCD1/PIPESTAT2_70") (pintype "passive"))
    )
    (net (code "95") (name "Net-(U8-P2.4{slash}PWM1.5{slash}DSR1{slash}TRACESYNC)") (class "Default")
      (node (ref "R138") (pin "1") (pinfunction "1_1") (pintype "passive"))
      (node (ref "U8") (pin "69") (pinfunction "P2.4/PWM1.5/DSR1/TRACESYNC_69") (pintype "passive"))
    )
    (net (code "96") (name "Net-(U8-P2.5{slash}PWM1.6{slash}DTR1{slash}TRACEPKT0)") (class "Default")
      (node (ref "R136") (pin "1") (pinfunction "1_1") (pintype "passive"))
      (node (ref "U8") (pin "68") (pinfunction "P2.5/PWM1.6/DTR1/TRACEPKT0_68") (pintype "passive"))
    )
    (net (code "97") (name "Net-(U8-P2.6{slash}PCAP1.0{slash}RI1{slash}TRACEPKT1)") (class "Default")
      (node (ref "R133") (pin "1") (pinfunction "1_1") (pintype "passive"))
      (node (ref "U8") (pin "67") (pinfunction "P2.6/PCAP1.0/RI1/TRACEPKT1_67") (pintype "passive"))
    )
    (net (code "98") (name "Net-(U8-P2.7{slash}RD2{slash}RTS1{slash}TRACEPKT2)") (class "Default")
      (node (ref "R132") (pin "1") (pinfunction "1_1") (pintype "passive"))
      (node (ref "U8") (pin "66") (pinfunction "P2.7/RD2/RTS1/TRACEPKT2_66") (pintype "passive"))
    )
    (net (code "99") (name "Net-(U8-P2.9{slash}USB_CONNECT{slash}RXD2{slash}EXTIN0)") (class "Default")
      (node (ref "R130") (pin "1") (pinfunction "1_1") (pintype "passive"))
      (node (ref "U8") (pin "64") (pinfunction "P2.9/USB_CONNECT/RXD2/EXTIN0_64") (pintype "passive"))
    )
    (net (code "100") (name "Net-(U8-P2.11{slash}~{EINT1}{slash}MCIDAT1{slash}I2STX_CLK)") (class "Default")
      (node (ref "R128") (pin "1") (pinfunction "1_1") (pintype "passive"))
      (node (ref "U8") (pin "52") (pinfunction "P2.11/~{EINT1}/MCIDAT1/I2STX_CLK_52") (pintype "passive"))
    )
    (net (code "101") (name "Net-(U8-P2.12{slash}~{EINT2}{slash}MCIDAT2{slash}I2STX_WS)") (class "Default")
      (node (ref "R126") (pin "1") (pinfunction "1_1") (pintype "passive"))
      (node (ref "U8") (pin "51") (pinfunction "P2.12/~{EINT2}/MCIDAT2/I2STX_WS_51") (pintype "passive"))
    )
    (net (code "102") (name "Net-(U8-P2.13{slash}~{EINT3}{slash}MCIDAT3{slash}I2STX_SDA)") (class "Default")
      (node (ref "R124") (pin "1") (pinfunction "1_1") (pintype "passive"))
      (node (ref "U8") (pin "50") (pinfunction "P2.13/~{EINT3}/MCIDAT3/I2STX_SDA_50") (pintype "passive"))
    )
    (net (code "103") (name "Net-(U8-P3.25{slash}MAT0.0{slash}PWM1.2)") (class "Default")
      (node (ref "R135") (pin "2") (pinfunction "2_2") (pintype "passive"))
      (node (ref "U8") (pin "27") (pinfunction "P3.25/MAT0.0/PWM1.2_27") (pintype "passive"))
    )
    (net (code "104") (name "Net-(U8-P3.26{slash}MAT0.1{slash}PWM1.3)") (class "Default")
      (node (ref "R137") (pin "2") (pinfunction "2_2") (pintype "passive"))
      (node (ref "U8") (pin "26") (pinfunction "P3.26/MAT0.1/PWM1.3_26") (pintype "passive"))
    )
    (net (code "105") (name "Net-(U8-P4.28{slash}MAT2.0{slash}TXD3)") (class "Default")
      (node (ref "R142") (pin "2") (pinfunction "2_2") (pintype "passive"))
      (node (ref "U8") (pin "82") (pinfunction "P4.28/MAT2.0/TXD3_82") (pintype "passive"))
    )
    (net (code "106") (name "Net-(U8-RTCK)") (class "Default")
      (node (ref "R95") (pin "1") (pinfunction "1_1") (pintype "passive"))
      (node (ref "U8") (pin "100") (pinfunction "RTCK_100") (pintype "passive"))
    )
    (net (code "107") (name "Net-(U8-RTCX1)") (class "Default")
      (node (ref "C78") (pin "2") (pinfunction "2_2") (pintype "passive"))
      (node (ref "U8") (pin "16") (pinfunction "RTCX1_16") (pintype "passive"))
      (node (ref "Y3") (pin "1") (pinfunction "OSC1_1") (pintype "passive"))
    )
    (net (code "108") (name "Net-(U8-RTCX2)") (class "Default")
      (node (ref "C80") (pin "2") (pinfunction "2_2") (pintype "passive"))
      (node (ref "U8") (pin "18") (pinfunction "RTCX2_18") (pintype "passive"))
      (node (ref "Y3") (pin "2") (pinfunction "OSC2_2") (pintype "passive"))
    )
    (net (code "109") (name "Net-(U8-VREF)") (class "Default")
      (node (ref "C92") (pin "2") (pinfunction "2_2") (pintype "passive"))
      (node (ref "C93") (pin "2") (pinfunction "2_2") (pintype "passive"))
      (node (ref "L13") (pin "1") (pinfunction "1_1") (pintype "passive"))
      (node (ref "U8") (pin "12") (pinfunction "VREF_12") (pintype "passive"))
    )
    (net (code "110") (name "Net-(U8-Vdcdc(3V3)_01--1768(NC))") (class "Default")
      (node (ref "R113") (pin "1") (pinfunction "1_1") (pintype "passive"))
      (node (ref "U8") (pin "13") (pinfunction "Vdcdc(3V3)_01--1768(NC)_13") (pintype "passive"))
    )
    (net (code "111") (name "Net-(U8-VddA)") (class "Default")
      (node (ref "C81") (pin "2") (pinfunction "2_2") (pintype "passive"))
      (node (ref "C82") (pin "2") (pinfunction "2_2") (pintype "passive"))
      (node (ref "L12") (pin "1") (pinfunction "1_1") (pintype "passive"))
      (node (ref "U8") (pin "10") (pinfunction "VddA_10") (pintype "passive"))
    )
    (net (code "112") (name "Net-(U8-X1)") (class "Default")
      (node (ref "C76") (pin "2") (pinfunction "2_2") (pintype "passive"))
      (node (ref "U8") (pin "22") (pinfunction "X1_22") (pintype "passive"))
      (node (ref "Y2") (pin "1") (pinfunction "OSC1_1") (pintype "passive"))
    )
    (net (code "113") (name "Net-(U8-X2)") (class "Default")
      (node (ref "C77") (pin "2") (pinfunction "2_2") (pintype "passive"))
      (node (ref "U8") (pin "23") (pinfunction "X2_23") (pintype "passive"))
      (node (ref "Y2") (pin "2") (pinfunction "OSC2_2") (pintype "passive"))
    )
    (net (code "114") (name "PHY_INTn") (class "Default")
      (node (ref "R104") (pin "1") (pinfunction "1_1") (pintype "passive"))
    )
    (net (code "115") (name "PHY_RST") (class "Default")
      (node (ref "R105") (pin "1") (pinfunction "1_1") (pintype "passive"))
    )
    (net (code "116") (name "SD_MCICD") (class "Default")
      (node (ref "U8") (pin "45") (pinfunction "P1.29/PCAP1.1/MAT0.1_45") (pintype "passive"))
    )
    (net (code "117") (name "SD_MCICLK") (class "Default")
      (node (ref "R100") (pin "1") (pinfunction "1_1") (pintype "passive"))
    )
    (net (code "118") (name "SD_MCICMD") (class "Default")
      (node (ref "R101") (pin "1") (pinfunction "1_1") (pintype "passive"))
    )
    (net (code "119") (name "SD_MCIDAT0") (class "Default")
      (node (ref "R103") (pin "1") (pinfunction "1_1") (pintype "passive"))
    )
    (net (code "120") (name "SD_MCIDAT1") (class "Default")
      (node (ref "R128") (pin "2") (pinfunction "2_2") (pintype "passive"))
    )
    (net (code "121") (name "SD_MCIDAT2") (class "Default")
      (node (ref "R126") (pin "2") (pinfunction "2_2") (pintype "passive"))
    )
    (net (code "122") (name "SD_MCIDAT3") (class "Default")
      (node (ref "R124") (pin "2") (pinfunction "2_2") (pintype "passive"))
    )
    (net (code "123") (name "SPI_MISO") (class "Default")
      (node (ref "U8") (pin "37") (pinfunction "P1.23/PWM1.4/MISO0_37") (pintype "passive"))
    )
    (net (code "124") (name "SPI_MOSI") (class "Default")
      (node (ref "R121") (pin "1") (pinfunction "1_1") (pintype "passive"))
    )
    (net (code "125") (name "SPI_SCK") (class "Default")
      (node (ref "R118") (pin "1") (pinfunction "1_1") (pintype "passive"))
    )
    (net (code "126") (name "SPI_SSEL") (class "Default")
      (node (ref "R119") (pin "1") (pinfunction "1_1") (pintype "passive"))
    )
    (net (code "127") (name "TR24_CE") (class "Default")
      (node (ref "R137") (pin "1") (pinfunction "1_1") (pintype "passive"))
    )
    (net (code "128") (name "TR24_CS") (class "Default")
      (node (ref "R127") (pin "1") (pinfunction "1_1") (pintype "passive"))
    )
    (net (code "129") (name "TR24_IRQ") (class "Default")
      (node (ref "R145") (pin "2") (pinfunction "2_2") (pintype "passive"))
    )
    (net (code "130") (name "USB_CONNECT") (class "Default")
      (node (ref "R130") (pin "2") (pinfunction "2_2") (pintype "passive"))
    )
    (net (code "131") (name "USB_D+") (class "Default")
      (node (ref "U8") (pin "29") (pinfunction "P0.29/U1D+_29") (pintype "passive"))
    )
    (net (code "132") (name "USB_D-") (class "Default")
      (node (ref "U8") (pin "30") (pinfunction "P0.30/U1D-_30") (pintype "passive"))
    )
    (net (code "133") (name "VBAT") (class "Default")
      (node (ref "U8") (pin "19") (pinfunction "VBAT_19") (pintype "passive"))
    )
    (net (code "134") (name "VBUS") (class "Default")
      (node (ref "R129") (pin "1") (pinfunction "1_1") (pintype "passive"))
    )
    (net (code "135") (name "VDD3V3") (class "Default")
      (node (ref "C74") (pin "2") (pinfunction "2_2") (pintype "passive"))
      (node (ref "C75") (pin "2") (pinfunction "2_2") (pintype "passive"))
      (node (ref "C83") (pin "2") (pinfunction "2_2") (pintype "passive"))
      (node (ref "C84") (pin "2") (pinfunction "2_2") (pintype "passive"))
      (node (ref "C85") (pin "2") (pinfunction "2_2") (pintype "passive"))
      (node (ref "C86") (pin "2") (pinfunction "2_2") (pintype "passive"))
      (node (ref "C87") (pin "2") (pinfunction "2_2") (pintype "passive"))
      (node (ref "C88") (pin "2") (pinfunction "2_2") (pintype "passive"))
      (node (ref "C89") (pin "2") (pinfunction "2_2") (pintype "passive"))
      (node (ref "C90") (pin "2") (pinfunction "2_2") (pintype "passive"))
      (node (ref "C91") (pin "2") (pinfunction "2_2") (pintype "passive"))
      (node (ref "C94") (pin "2") (pinfunction "2_2") (pintype "passive"))
      (node (ref "D11") (pin "A") (pinfunction "A_A") (pintype "passive"))
      (node (ref "D3") (pin "A") (pinfunction "A_A") (pintype "passive"))
      (node (ref "JP1") (pin "1") (pinfunction "VCC_1") (pintype "passive"))
      (node (ref "JP1") (pin "2") (pinfunction "VCC_2") (pintype "passive"))
      (node (ref "L12") (pin "2") (pinfunction "2_2") (pintype "passive"))
      (node (ref "L13") (pin "2") (pinfunction "2_2") (pintype "passive"))
      (node (ref "R106") (pin "2") (pinfunction "2_2") (pintype "passive"))
      (node (ref "R108") (pin "2") (pinfunction "2_2") (pintype "passive"))
      (node (ref "R113") (pin "2") (pinfunction "2_2") (pintype "passive"))
      (node (ref "R134") (pin "2") (pinfunction "2_2") (pintype "passive"))
      (node (ref "R87") (pin "2") (pinfunction "2_2") (pintype "passive"))
      (node (ref "R88") (pin "2") (pinfunction "2_2") (pintype "passive"))
      (node (ref "R89") (pin "2") (pinfunction "2_2") (pintype "passive"))
      (node (ref "R90") (pin "2") (pinfunction "2_2") (pintype "passive"))
      (node (ref "R91") (pin "2") (pinfunction "2_2") (pintype "passive"))
      (node (ref "R95") (pin "2") (pinfunction "2_2") (pintype "passive"))
      (node (ref "R98") (pin "2") (pinfunction "2_2") (pintype "passive"))
      (node (ref "U8") (pin "28") (pinfunction "Vdd(3V3)_01_28") (pintype "passive"))
      (node (ref "U8") (pin "42") (pinfunction "Vdcdc(3V3)_02_42") (pintype "passive"))
      (node (ref "U8") (pin "54") (pinfunction "Vdd(3V3)_02_54") (pintype "passive"))
      (node (ref "U8") (pin "71") (pinfunction "Vdd(3V3)_03_71") (pintype "passive"))
      (node (ref "U8") (pin "84") (pinfunction "Vdcdc(3V3)_03_84") (pintype "passive"))
      (node (ref "U8") (pin "96") (pinfunction "Vdd(3V3)_04_96") (pintype "passive"))
    )
    (net (code "136") (name "VDD5V") (class "Default")
      (node (ref "C95") (pin "2") (pinfunction "2_2") (pintype "passive"))
      (node (ref "C96") (pin "2") (pinfunction "2_2") (pintype "passive"))
      (node (ref "P5") (pin "1") (pinfunction "1_1") (pintype "passive"))
      (node (ref "P5") (pin "2") (pinfunction "2_2") (pintype "passive"))
    )
    (net (code "137") (name "unconnected-(JP1-NC-Pad17)") (class "Default")
      (node (ref "JP1") (pin "17") (pinfunction "NC_17") (pintype "passive+no_connect"))
    )
    (net (code "138") (name "unconnected-(JP1-NC-Pad19)") (class "Default")
      (node (ref "JP1") (pin "19") (pinfunction "NC_19") (pintype "passive+no_connect"))
    )
    (net (code "139") (name "unconnected-(U8-~{RSTOUT}-Pad14)") (class "Default")
      (node (ref "U8") (pin "14") (pinfunction "~{RSTOUT}_14") (pintype "passive+no_connect"))
    )
  )
)
